# RPi_Extension_breakout_jetson.net
KiCad netlist of a schematic drawn in EAGLE
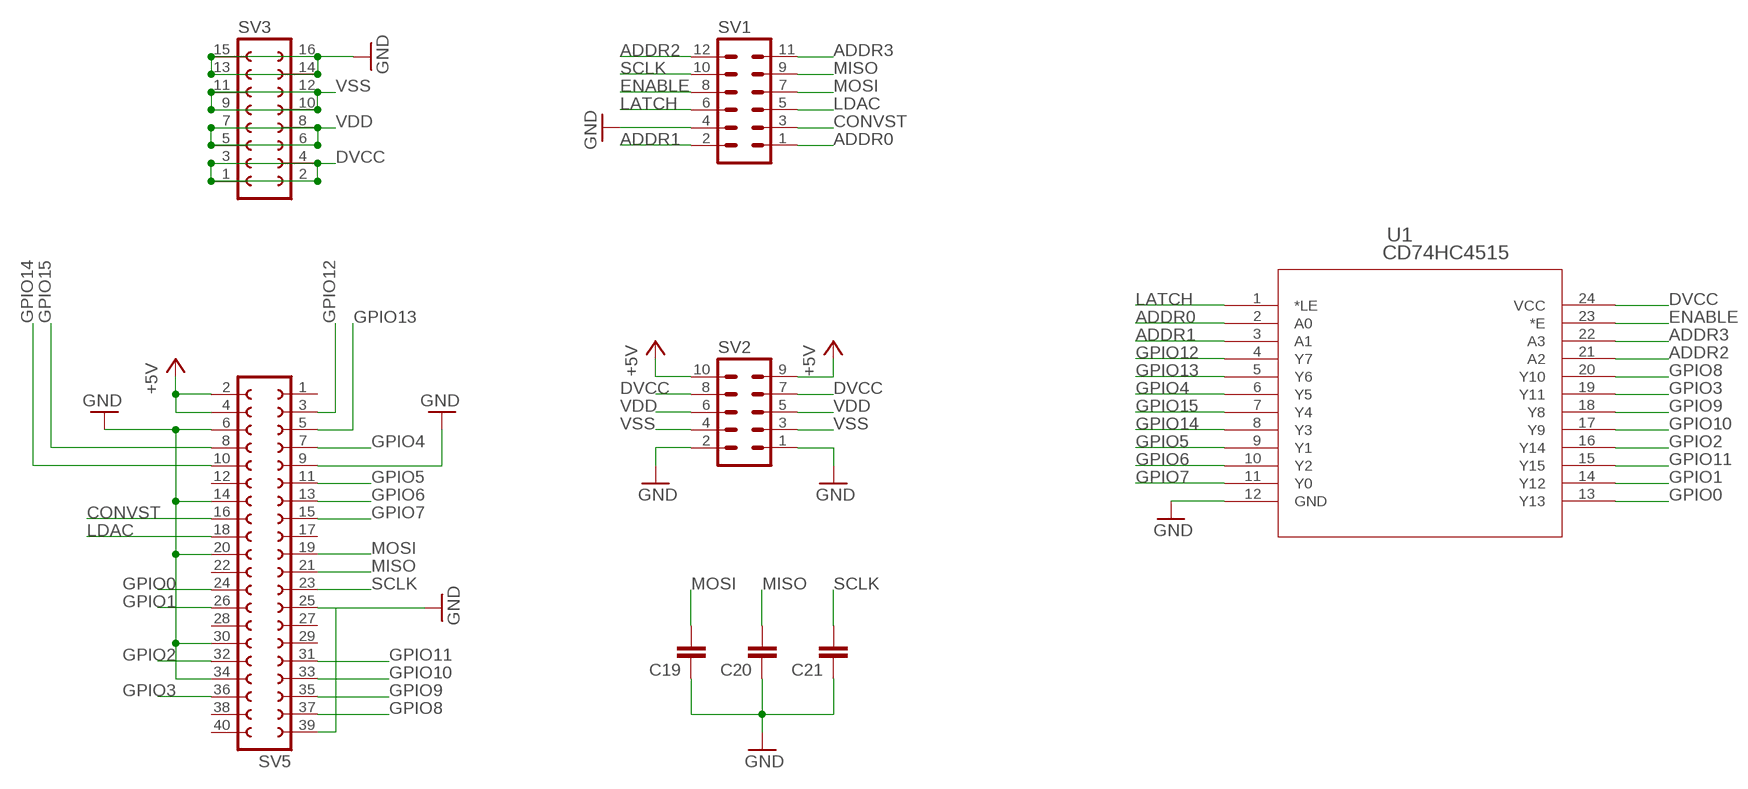
[diagram p0: schematic, sheet 1]

(export (version "E")
  (design (tool "Eeschema 10.0.6"))
  (components
    (comp (ref "C19")
      (value "C-EUC0603")
      (footprint "eagle-import:C0603")
      (libsource (lib "eagle-import") (part "C-EUC0603"))
    )
    (comp (ref "C20")
      (value "C-EUC0603")
      (footprint "eagle-import:C0603")
      (libsource (lib "eagle-import") (part "C-EUC0603"))
    )
    (comp (ref "C21")
      (value "C-EUC0603")
      (footprint "eagle-import:C0603")
      (libsource (lib "eagle-import") (part "C-EUC0603"))
    )
    (comp (ref "SV1")
      (value "MA06-2")
      (footprint "eagle-import:MA06-2")
      (libsource (lib "eagle-import") (part "MA06-2"))
    )
    (comp (ref "SV2")
      (value "MA05-2")
      (footprint "eagle-import:MA05-2")
      (libsource (lib "eagle-import") (part "MA05-2"))
    )
    (comp (ref "SV3")
      (value "FE08-2")
      (footprint "eagle-import:FE08-2")
      (libsource (lib "eagle-import") (part "FE08-2"))
    )
    (comp (ref "SV5")
      (value "FE20-2")
      (footprint "eagle-import:FE20-2")
      (libsource (lib "eagle-import") (part "FE20-2"))
    )
    (comp (ref "U1")
      (value "CD74HC4515")
      (footprint "eagle-import:DW24")
      (fields (field (name "MANUFACTURER") "Texas Instruments"))
      (libsource (lib "eagle-import") (part "CD74HC4515_DW_24"))
    )
  )
  (nets
    (net (code "1") (name "+5V") (class "Default")
      (node (ref "SV2") (pin "10") (pinfunction "10_10") (pintype "passive"))
      (node (ref "SV2") (pin "9") (pinfunction "9_9") (pintype "passive"))
      (node (ref "SV5") (pin "2") (pinfunction "2_2") (pintype "passive"))
      (node (ref "SV5") (pin "4") (pinfunction "4_4") (pintype "passive"))
    )
    (net (code "2") (name "/ADDR0") (class "Default")
      (node (ref "SV1") (pin "1") (pinfunction "1_1") (pintype "passive"))
      (node (ref "U1") (pin "2") (pinfunction "A0_2") (pintype "input"))
    )
    (net (code "3") (name "/ADDR1") (class "Default")
      (node (ref "SV1") (pin "2") (pinfunction "2_2") (pintype "passive"))
      (node (ref "U1") (pin "3") (pinfunction "A1_3") (pintype "input"))
    )
    (net (code "4") (name "/ADDR2") (class "Default")
      (node (ref "SV1") (pin "12") (pinfunction "12_12") (pintype "passive"))
      (node (ref "U1") (pin "21") (pinfunction "A2_21") (pintype "input"))
    )
    (net (code "5") (name "/ADDR3") (class "Default")
      (node (ref "SV1") (pin "11") (pinfunction "11_11") (pintype "passive"))
      (node (ref "U1") (pin "22") (pinfunction "A3_22") (pintype "input"))
    )
    (net (code "6") (name "/CONVST") (class "Default")
      (node (ref "SV1") (pin "3") (pinfunction "3_3") (pintype "passive"))
      (node (ref "SV5") (pin "16") (pinfunction "16_16") (pintype "passive"))
    )
    (net (code "7") (name "/DVCC") (class "Default")
      (node (ref "SV2") (pin "7") (pinfunction "7_7") (pintype "passive"))
      (node (ref "SV2") (pin "8") (pinfunction "8_8") (pintype "passive"))
      (node (ref "SV3") (pin "1") (pinfunction "1_1") (pintype "passive"))
      (node (ref "SV3") (pin "2") (pinfunction "2_2") (pintype "passive"))
      (node (ref "SV3") (pin "3") (pinfunction "3_3") (pintype "passive"))
      (node (ref "SV3") (pin "4") (pinfunction "4_4") (pintype "passive"))
      (node (ref "U1") (pin "24") (pinfunction "VCC_24") (pintype "power_in"))
    )
    (net (code "8") (name "/ENABLE") (class "Default")
      (node (ref "SV1") (pin "8") (pinfunction "8_8") (pintype "passive"))
      (node (ref "U1") (pin "23") (pinfunction "*E_23") (pintype "input"))
    )
    (net (code "9") (name "/GPIO0") (class "Default")
      (node (ref "SV5") (pin "24") (pinfunction "24_24") (pintype "passive"))
      (node (ref "U1") (pin "13") (pinfunction "Y13_13") (pintype "output"))
    )
    (net (code "10") (name "/GPIO1") (class "Default")
      (node (ref "SV5") (pin "26") (pinfunction "26_26") (pintype "passive"))
      (node (ref "U1") (pin "14") (pinfunction "Y12_14") (pintype "output"))
    )
    (net (code "11") (name "/GPIO2") (class "Default")
      (node (ref "SV5") (pin "32") (pinfunction "32_32") (pintype "passive"))
      (node (ref "U1") (pin "16") (pinfunction "Y14_16") (pintype "output"))
    )
    (net (code "12") (name "/GPIO3") (class "Default")
      (node (ref "SV5") (pin "36") (pinfunction "36_36") (pintype "passive"))
      (node (ref "U1") (pin "19") (pinfunction "Y11_19") (pintype "output"))
    )
    (net (code "13") (name "/GPIO4") (class "Default")
      (node (ref "SV5") (pin "7") (pinfunction "7_7") (pintype "passive"))
      (node (ref "U1") (pin "6") (pinfunction "Y5_6") (pintype "output"))
    )
    (net (code "14") (name "/GPIO5") (class "Default")
      (node (ref "SV5") (pin "11") (pinfunction "11_11") (pintype "passive"))
      (node (ref "U1") (pin "9") (pinfunction "Y1_9") (pintype "output"))
    )
    (net (code "15") (name "/GPIO6") (class "Default")
      (node (ref "SV5") (pin "13") (pinfunction "13_13") (pintype "passive"))
      (node (ref "U1") (pin "10") (pinfunction "Y2_10") (pintype "output"))
    )
    (net (code "16") (name "/GPIO7") (class "Default")
      (node (ref "SV5") (pin "15") (pinfunction "15_15") (pintype "passive"))
      (node (ref "U1") (pin "11") (pinfunction "Y0_11") (pintype "output"))
    )
    (net (code "17") (name "/GPIO8") (class "Default")
      (node (ref "SV5") (pin "37") (pinfunction "37_37") (pintype "passive"))
      (node (ref "U1") (pin "20") (pinfunction "Y10_20") (pintype "output"))
    )
    (net (code "18") (name "/GPIO9") (class "Default")
      (node (ref "SV5") (pin "35") (pinfunction "35_35") (pintype "passive"))
      (node (ref "U1") (pin "18") (pinfunction "Y8_18") (pintype "output"))
    )
    (net (code "19") (name "/GPIO10") (class "Default")
      (node (ref "SV5") (pin "33") (pinfunction "33_33") (pintype "passive"))
      (node (ref "U1") (pin "17") (pinfunction "Y9_17") (pintype "output"))
    )
    (net (code "20") (name "/GPIO11") (class "Default")
      (node (ref "SV5") (pin "31") (pinfunction "31_31") (pintype "passive"))
      (node (ref "U1") (pin "15") (pinfunction "Y15_15") (pintype "output"))
    )
    (net (code "21") (name "/GPIO12") (class "Default")
      (node (ref "SV5") (pin "3") (pinfunction "3_3") (pintype "passive"))
      (node (ref "U1") (pin "4") (pinfunction "Y7_4") (pintype "output"))
    )
    (net (code "22") (name "/GPIO13") (class "Default")
      (node (ref "SV5") (pin "5") (pinfunction "5_5") (pintype "passive"))
      (node (ref "U1") (pin "5") (pinfunction "Y6_5") (pintype "output"))
    )
    (net (code "23") (name "/GPIO14") (class "Default")
      (node (ref "SV5") (pin "10") (pinfunction "10_10") (pintype "passive"))
      (node (ref "U1") (pin "8") (pinfunction "Y3_8") (pintype "output"))
    )
    (net (code "24") (name "/GPIO15") (class "Default")
      (node (ref "SV5") (pin "8") (pinfunction "8_8") (pintype "passive"))
      (node (ref "U1") (pin "7") (pinfunction "Y4_7") (pintype "output"))
    )
    (net (code "25") (name "/LATCH") (class "Default")
      (node (ref "SV1") (pin "6") (pinfunction "6_6") (pintype "passive"))
      (node (ref "U1") (pin "1") (pinfunction "*LE_1") (pintype "input"))
    )
    (net (code "26") (name "/LDAC") (class "Default")
      (node (ref "SV1") (pin "5") (pinfunction "5_5") (pintype "passive"))
      (node (ref "SV5") (pin "18") (pinfunction "18_18") (pintype "passive"))
    )
    (net (code "27") (name "/MISO") (class "Default")
      (node (ref "C20") (pin "2") (pinfunction "2_2") (pintype "passive"))
      (node (ref "SV1") (pin "9") (pinfunction "9_9") (pintype "passive"))
      (node (ref "SV5") (pin "21") (pinfunction "21_21") (pintype "passive"))
    )
    (net (code "28") (name "/MOSI") (class "Default")
      (node (ref "C19") (pin "2") (pinfunction "2_2") (pintype "passive"))
      (node (ref "SV1") (pin "7") (pinfunction "7_7") (pintype "passive"))
      (node (ref "SV5") (pin "19") (pinfunction "19_19") (pintype "passive"))
    )
    (net (code "29") (name "/SCLK") (class "Default")
      (node (ref "C21") (pin "2") (pinfunction "2_2") (pintype "passive"))
      (node (ref "SV1") (pin "10") (pinfunction "10_10") (pintype "passive"))
      (node (ref "SV5") (pin "23") (pinfunction "23_23") (pintype "passive"))
    )
    (net (code "30") (name "/VDD") (class "Default")
      (node (ref "SV2") (pin "5") (pinfunction "5_5") (pintype "passive"))
      (node (ref "SV2") (pin "6") (pinfunction "6_6") (pintype "passive"))
      (node (ref "SV3") (pin "5") (pinfunction "5_5") (pintype "passive"))
      (node (ref "SV3") (pin "6") (pinfunction "6_6") (pintype "passive"))
      (node (ref "SV3") (pin "7") (pinfunction "7_7") (pintype "passive"))
      (node (ref "SV3") (pin "8") (pinfunction "8_8") (pintype "passive"))
    )
    (net (code "31") (name "/VSS") (class "Default")
      (node (ref "SV2") (pin "3") (pinfunction "3_3") (pintype "passive"))
      (node (ref "SV2") (pin "4") (pinfunction "4_4") (pintype "passive"))
      (node (ref "SV3") (pin "10") (pinfunction "10_10") (pintype "passive"))
      (node (ref "SV3") (pin "11") (pinfunction "11_11") (pintype "passive"))
      (node (ref "SV3") (pin "12") (pinfunction "12_12") (pintype "passive"))
      (node (ref "SV3") (pin "9") (pinfunction "9_9") (pintype "passive"))
    )
    (net (code "32") (name "GND") (class "Default")
      (node (ref "C19") (pin "1") (pinfunction "1_1") (pintype "passive"))
      (node (ref "C20") (pin "1") (pinfunction "1_1") (pintype "passive"))
      (node (ref "C21") (pin "1") (pinfunction "1_1") (pintype "passive"))
      (node (ref "SV1") (pin "4") (pinfunction "4_4") (pintype "passive"))
      (node (ref "SV2") (pin "1") (pinfunction "1_1") (pintype "passive"))
      (node (ref "SV2") (pin "2") (pinfunction "2_2") (pintype "passive"))
      (node (ref "SV3") (pin "13") (pinfunction "13_13") (pintype "passive"))
      (node (ref "SV3") (pin "14") (pinfunction "14_14") (pintype "passive"))
      (node (ref "SV3") (pin "15") (pinfunction "15_15") (pintype "passive"))
      (node (ref "SV3") (pin "16") (pinfunction "16_16") (pintype "passive"))
      (node (ref "SV5") (pin "14") (pinfunction "14_14") (pintype "passive"))
      (node (ref "SV5") (pin "20") (pinfunction "20_20") (pintype "passive"))
      (node (ref "SV5") (pin "25") (pinfunction "25_25") (pintype "passive"))
      (node (ref "SV5") (pin "30") (pinfunction "30_30") (pintype "passive"))
      (node (ref "SV5") (pin "34") (pinfunction "34_34") (pintype "passive"))
      (node (ref "SV5") (pin "39") (pinfunction "39_39") (pintype "passive"))
      (node (ref "SV5") (pin "6") (pinfunction "6_6") (pintype "passive"))
      (node (ref "SV5") (pin "9") (pinfunction "9_9") (pintype "passive"))
      (node (ref "U1") (pin "12") (pinfunction "GND_12") (pintype "power_in"))
    )
    (net (code "33") (name "unconnected-(SV5-Pad1)") (class "Default")
      (node (ref "SV5") (pin "1") (pinfunction "1_1") (pintype "passive"))
    )
    (net (code "34") (name "unconnected-(SV5-Pad12)") (class "Default")
      (node (ref "SV5") (pin "12") (pinfunction "12_12") (pintype "passive"))
    )
    (net (code "35") (name "unconnected-(SV5-Pad17)") (class "Default")
      (node (ref "SV5") (pin "17") (pinfunction "17_17") (pintype "passive"))
    )
    (net (code "36") (name "unconnected-(SV5-Pad22)") (class "Default")
      (node (ref "SV5") (pin "22") (pinfunction "22_22") (pintype "passive"))
    )
    (net (code "37") (name "unconnected-(SV5-Pad27)") (class "Default")
      (node (ref "SV5") (pin "27") (pinfunction "27_27") (pintype "passive"))
    )
    (net (code "38") (name "unconnected-(SV5-Pad28)") (class "Default")
      (node (ref "SV5") (pin "28") (pinfunction "28_28") (pintype "passive"))
    )
    (net (code "39") (name "unconnected-(SV5-Pad29)") (class "Default")
      (node (ref "SV5") (pin "29") (pinfunction "29_29") (pintype "passive"))
    )
    (net (code "40") (name "unconnected-(SV5-Pad38)") (class "Default")
      (node (ref "SV5") (pin "38") (pinfunction "38_38") (pintype "passive"))
    )
    (net (code "41") (name "unconnected-(SV5-Pad40)") (class "Default")
      (node (ref "SV5") (pin "40") (pinfunction "40_40") (pintype "passive"))
    )
  )
)
